# testjig.net
KiCad netlist of a schematic drawn in EAGLE
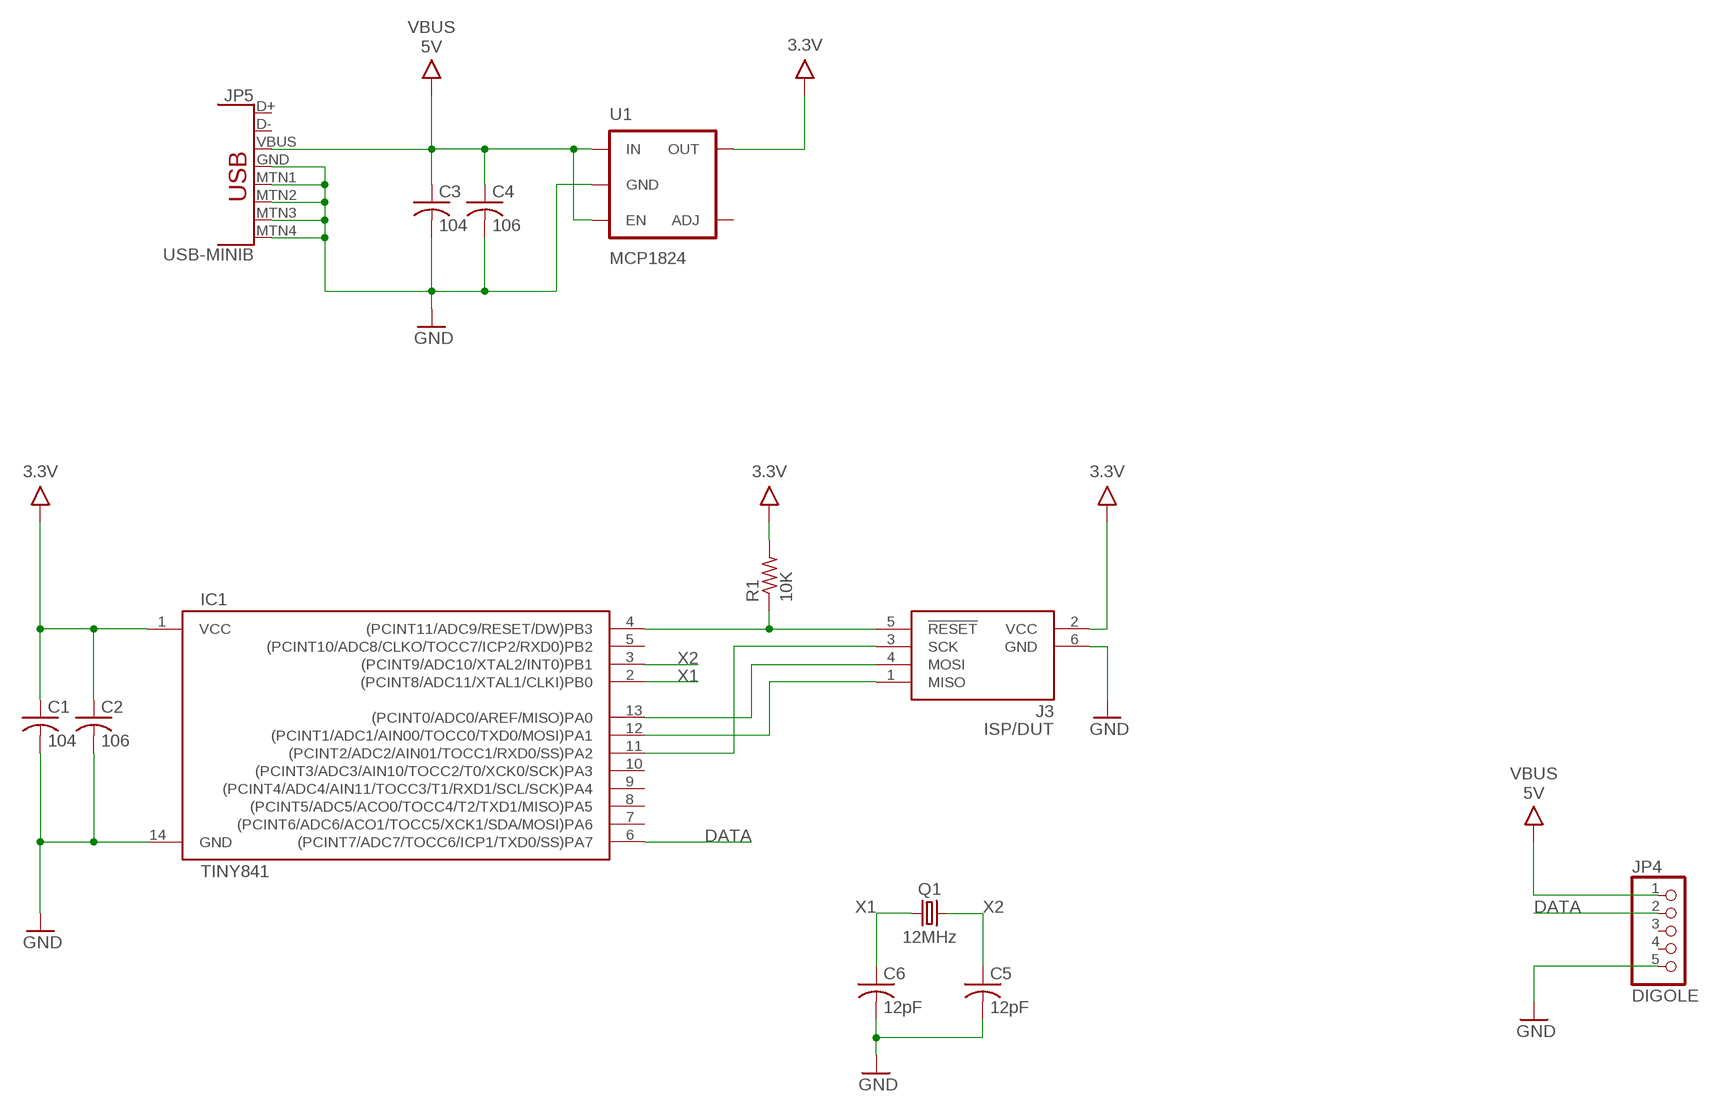
[diagram p0: schematic, sheet 1]

(export (version "E")
  (design (tool "Eeschema 10.0.6"))
  (components
    (comp (ref "C1")
      (value "104")
      (footprint "eagle-import:0603")
      (libsource (lib "eagle-import") (part "C-0603"))
    )
    (comp (ref "C2")
      (value "106")
      (footprint "eagle-import:0603")
      (libsource (lib "eagle-import") (part "C-0603"))
    )
    (comp (ref "C3")
      (value "104")
      (footprint "eagle-import:0603")
      (libsource (lib "eagle-import") (part "C-0603"))
    )
    (comp (ref "C4")
      (value "106")
      (footprint "eagle-import:0603")
      (libsource (lib "eagle-import") (part "C-0603"))
    )
    (comp (ref "C5")
      (value "12pF")
      (footprint "eagle-import:0603")
      (libsource (lib "eagle-import") (part "C-0603"))
    )
    (comp (ref "C6")
      (value "12pF")
      (footprint "eagle-import:0603")
      (libsource (lib "eagle-import") (part "C-0603"))
    )
    (comp (ref "IC1")
      (value "TINY841")
      (footprint "eagle-import:SOIC14N")
      (libsource (lib "eagle-import") (part "ATTINY441/841-SSU"))
    )
    (comp (ref "J3")
      (value "ISP/DUT")
      (footprint "eagle-import:CON6P2R")
      (libsource (lib "eagle-import") (part "AVRISP6_COMPACT"))
    )
    (comp (ref "JP4")
      (value "DIGOLE")
      (footprint "eagle-import:1X05-S")
      (libsource (lib "eagle-import") (part "PINHD-1X05_2.54-S"))
    )
    (comp (ref "JP5")
      (value "USB-MINIB")
      (footprint "eagle-import:USB-MINIB")
      (libsource (lib "eagle-import") (part "USB-MINIB"))
    )
    (comp (ref "Q1")
      (value "12MHz")
      (footprint "eagle-import:NDK_2PAD_5X3")
      (libsource (lib "eagle-import") (part "CRYSTALNDK5X3"))
    )
    (comp (ref "R1")
      (value "10K")
      (footprint "eagle-import:0603")
      (libsource (lib "eagle-import") (part "R0603"))
    )
    (comp (ref "U1")
      (value "MCP1824")
      (footprint "eagle-import:SOT23-5")
      (libsource (lib "eagle-import") (part "MCP1824"))
    )
  )
  (nets
    (net (code "1") (name "/DATA") (class "Default")
      (node (ref "IC1") (pin "6") (pinfunction "(PCINT7/ADC7/TOCC6/ICP1/TXD0/SS)PA7_6") (pintype "bidirectional"))
      (node (ref "JP4") (pin "2") (pinfunction "2_2") (pintype "passive"))
    )
    (net (code "2") (name "/X1") (class "Default")
      (node (ref "C6") (pin "1") (pinfunction "+_1") (pintype "passive"))
      (node (ref "IC1") (pin "2") (pinfunction "(PCINT8/ADC11/XTAL1/CLKI)PB0_2") (pintype "bidirectional"))
      (node (ref "Q1") (pin "P$1") (pinfunction "1_P$1") (pintype "passive"))
    )
    (net (code "3") (name "/X2") (class "Default")
      (node (ref "C5") (pin "1") (pinfunction "+_1") (pintype "passive"))
      (node (ref "IC1") (pin "3") (pinfunction "(PCINT9/ADC10/XTAL2/INT0)PB1_3") (pintype "bidirectional"))
      (node (ref "Q1") (pin "P$2") (pinfunction "2_P$2") (pintype "passive"))
    )
    (net (code "4") (name "3.3V") (class "Default")
      (node (ref "C1") (pin "1") (pinfunction "+_1") (pintype "passive"))
      (node (ref "C2") (pin "1") (pinfunction "+_1") (pintype "passive"))
      (node (ref "IC1") (pin "1") (pinfunction "VCC_1") (pintype "bidirectional"))
      (node (ref "J3") (pin "2") (pinfunction "VCC_2") (pintype "power_in"))
      (node (ref "R1") (pin "2") (pinfunction "2_2") (pintype "passive"))
      (node (ref "U1") (pin "5") (pinfunction "OUT_5") (pintype "passive"))
    )
    (net (code "5") (name "5V") (class "Default")
      (node (ref "C3") (pin "1") (pinfunction "+_1") (pintype "passive"))
      (node (ref "C4") (pin "1") (pinfunction "+_1") (pintype "passive"))
      (node (ref "JP4") (pin "1") (pinfunction "1_1") (pintype "passive"))
      (node (ref "JP5") (pin "VBUS") (pinfunction "VBUS_VBUS") (pintype "bidirectional"))
      (node (ref "U1") (pin "1") (pinfunction "IN_1") (pintype "input"))
      (node (ref "U1") (pin "3") (pinfunction "EN_3") (pintype "input"))
    )
    (net (code "6") (name "GND") (class "Default")
      (node (ref "C1") (pin "2") (pinfunction "-_2") (pintype "passive"))
      (node (ref "C2") (pin "2") (pinfunction "-_2") (pintype "passive"))
      (node (ref "C3") (pin "2") (pinfunction "-_2") (pintype "passive"))
      (node (ref "C4") (pin "2") (pinfunction "-_2") (pintype "passive"))
      (node (ref "C5") (pin "2") (pinfunction "-_2") (pintype "passive"))
      (node (ref "C6") (pin "2") (pinfunction "-_2") (pintype "passive"))
      (node (ref "IC1") (pin "14") (pinfunction "GND_14") (pintype "bidirectional"))
      (node (ref "J3") (pin "6") (pinfunction "GND_6") (pintype "power_in"))
      (node (ref "JP4") (pin "5") (pinfunction "5_5") (pintype "passive"))
      (node (ref "JP5") (pin "GND") (pinfunction "GND_GND") (pintype "bidirectional"))
      (node (ref "JP5") (pin "MTN1") (pinfunction "SHIELD1_MTN1") (pintype "bidirectional"))
      (node (ref "JP5") (pin "MTN2") (pinfunction "SHIELD2_MTN2") (pintype "bidirectional"))
      (node (ref "JP5") (pin "MTN3") (pinfunction "SHIELD3_MTN3") (pintype "bidirectional"))
      (node (ref "JP5") (pin "MTN4") (pinfunction "SHIELD4_MTN4") (pintype "bidirectional"))
      (node (ref "U1") (pin "2") (pinfunction "GND_2") (pintype "input"))
    )
    (net (code "7") (name "Net-(IC1-(PCINT0{slash}ADC0{slash}AREF{slash}MISO)PA0)") (class "Default")
      (node (ref "IC1") (pin "13") (pinfunction "(PCINT0/ADC0/AREF/MISO)PA0_13") (pintype "bidirectional"))
      (node (ref "J3") (pin "4") (pinfunction "MOSI_4") (pintype "output"))
    )
    (net (code "8") (name "Net-(IC1-(PCINT1{slash}ADC1{slash}AIN00{slash}TOCC0{slash}TXD0{slash}MOSI)PA1)") (class "Default")
      (node (ref "IC1") (pin "12") (pinfunction "(PCINT1/ADC1/AIN00/TOCC0/TXD0/MOSI)PA1_12") (pintype "bidirectional"))
      (node (ref "J3") (pin "1") (pinfunction "MISO_1") (pintype "input"))
    )
    (net (code "9") (name "Net-(IC1-(PCINT2{slash}ADC2{slash}AIN01{slash}TOCC1{slash}RXD0{slash}SS)PA2)") (class "Default")
      (node (ref "IC1") (pin "11") (pinfunction "(PCINT2/ADC2/AIN01/TOCC1/RXD0/SS)PA2_11") (pintype "bidirectional"))
      (node (ref "J3") (pin "3") (pinfunction "SCK_3") (pintype "output"))
    )
    (net (code "10") (name "Net-(IC1-(PCINT11{slash}ADC9{slash}RESET{slash}DW)PB3)") (class "Default")
      (node (ref "IC1") (pin "4") (pinfunction "(PCINT11/ADC9/RESET/DW)PB3_4") (pintype "bidirectional"))
      (node (ref "J3") (pin "5") (pinfunction "~{RESET}_5") (pintype "output"))
      (node (ref "R1") (pin "1") (pinfunction "1_1") (pintype "passive"))
    )
    (net (code "11") (name "unconnected-(IC1-(PCINT3{slash}ADC3{slash}AIN10{slash}TOCC2{slash}T0{slash}XCK0{slash}SCK)PA3-Pad10)") (class "Default")
      (node (ref "IC1") (pin "10") (pinfunction "(PCINT3/ADC3/AIN10/TOCC2/T0/XCK0/SCK)PA3_10") (pintype "bidirectional"))
    )
    (net (code "12") (name "unconnected-(IC1-(PCINT4{slash}ADC4{slash}AIN11{slash}TOCC3{slash}T1{slash}RXD1{slash}SCL{slash}SCK)PA4-Pad9)") (class "Default")
      (node (ref "IC1") (pin "9") (pinfunction "(PCINT4/ADC4/AIN11/TOCC3/T1/RXD1/SCL/SCK)PA4_9") (pintype "bidirectional"))
    )
    (net (code "13") (name "unconnected-(IC1-(PCINT5{slash}ADC5{slash}ACO0{slash}TOCC4{slash}T2{slash}TXD1{slash}MISO)PA5-Pad8)") (class "Default")
      (node (ref "IC1") (pin "8") (pinfunction "(PCINT5/ADC5/ACO0/TOCC4/T2/TXD1/MISO)PA5_8") (pintype "bidirectional"))
    )
    (net (code "14") (name "unconnected-(IC1-(PCINT6{slash}ADC6{slash}ACO1{slash}TOCC5{slash}XCK1{slash}SDA{slash}MOSI)PA6-Pad7)") (class "Default")
      (node (ref "IC1") (pin "7") (pinfunction "(PCINT6/ADC6/ACO1/TOCC5/XCK1/SDA/MOSI)PA6_7") (pintype "bidirectional"))
    )
    (net (code "15") (name "unconnected-(IC1-(PCINT10{slash}ADC8{slash}CLKO{slash}TOCC7{slash}ICP2{slash}RXD0)PB2-Pad5)") (class "Default")
      (node (ref "IC1") (pin "5") (pinfunction "(PCINT10/ADC8/CLKO/TOCC7/ICP2/RXD0)PB2_5") (pintype "bidirectional"))
    )
    (net (code "16") (name "unconnected-(JP4-Pad3)") (class "Default")
      (node (ref "JP4") (pin "3") (pinfunction "3_3") (pintype "passive"))
    )
    (net (code "17") (name "unconnected-(JP4-Pad4)") (class "Default")
      (node (ref "JP4") (pin "4") (pinfunction "4_4") (pintype "passive"))
    )
    (net (code "18") (name "unconnected-(JP5-PadD+)") (class "Default")
      (node (ref "JP5") (pin "D+") (pinfunction "D+_D+") (pintype "bidirectional"))
    )
    (net (code "19") (name "unconnected-(JP5-PadD-)") (class "Default")
      (node (ref "JP5") (pin "D-") (pinfunction "D-_D-") (pintype "bidirectional"))
    )
    (net (code "20") (name "unconnected-(U1-ADJ-Pad4)") (class "Default")
      (node (ref "U1") (pin "4") (pinfunction "ADJ_4") (pintype "input"))
    )
  )
)
